# TCRT1010_VIS_pac.net
KiCad netlist of a schematic drawn in EAGLE
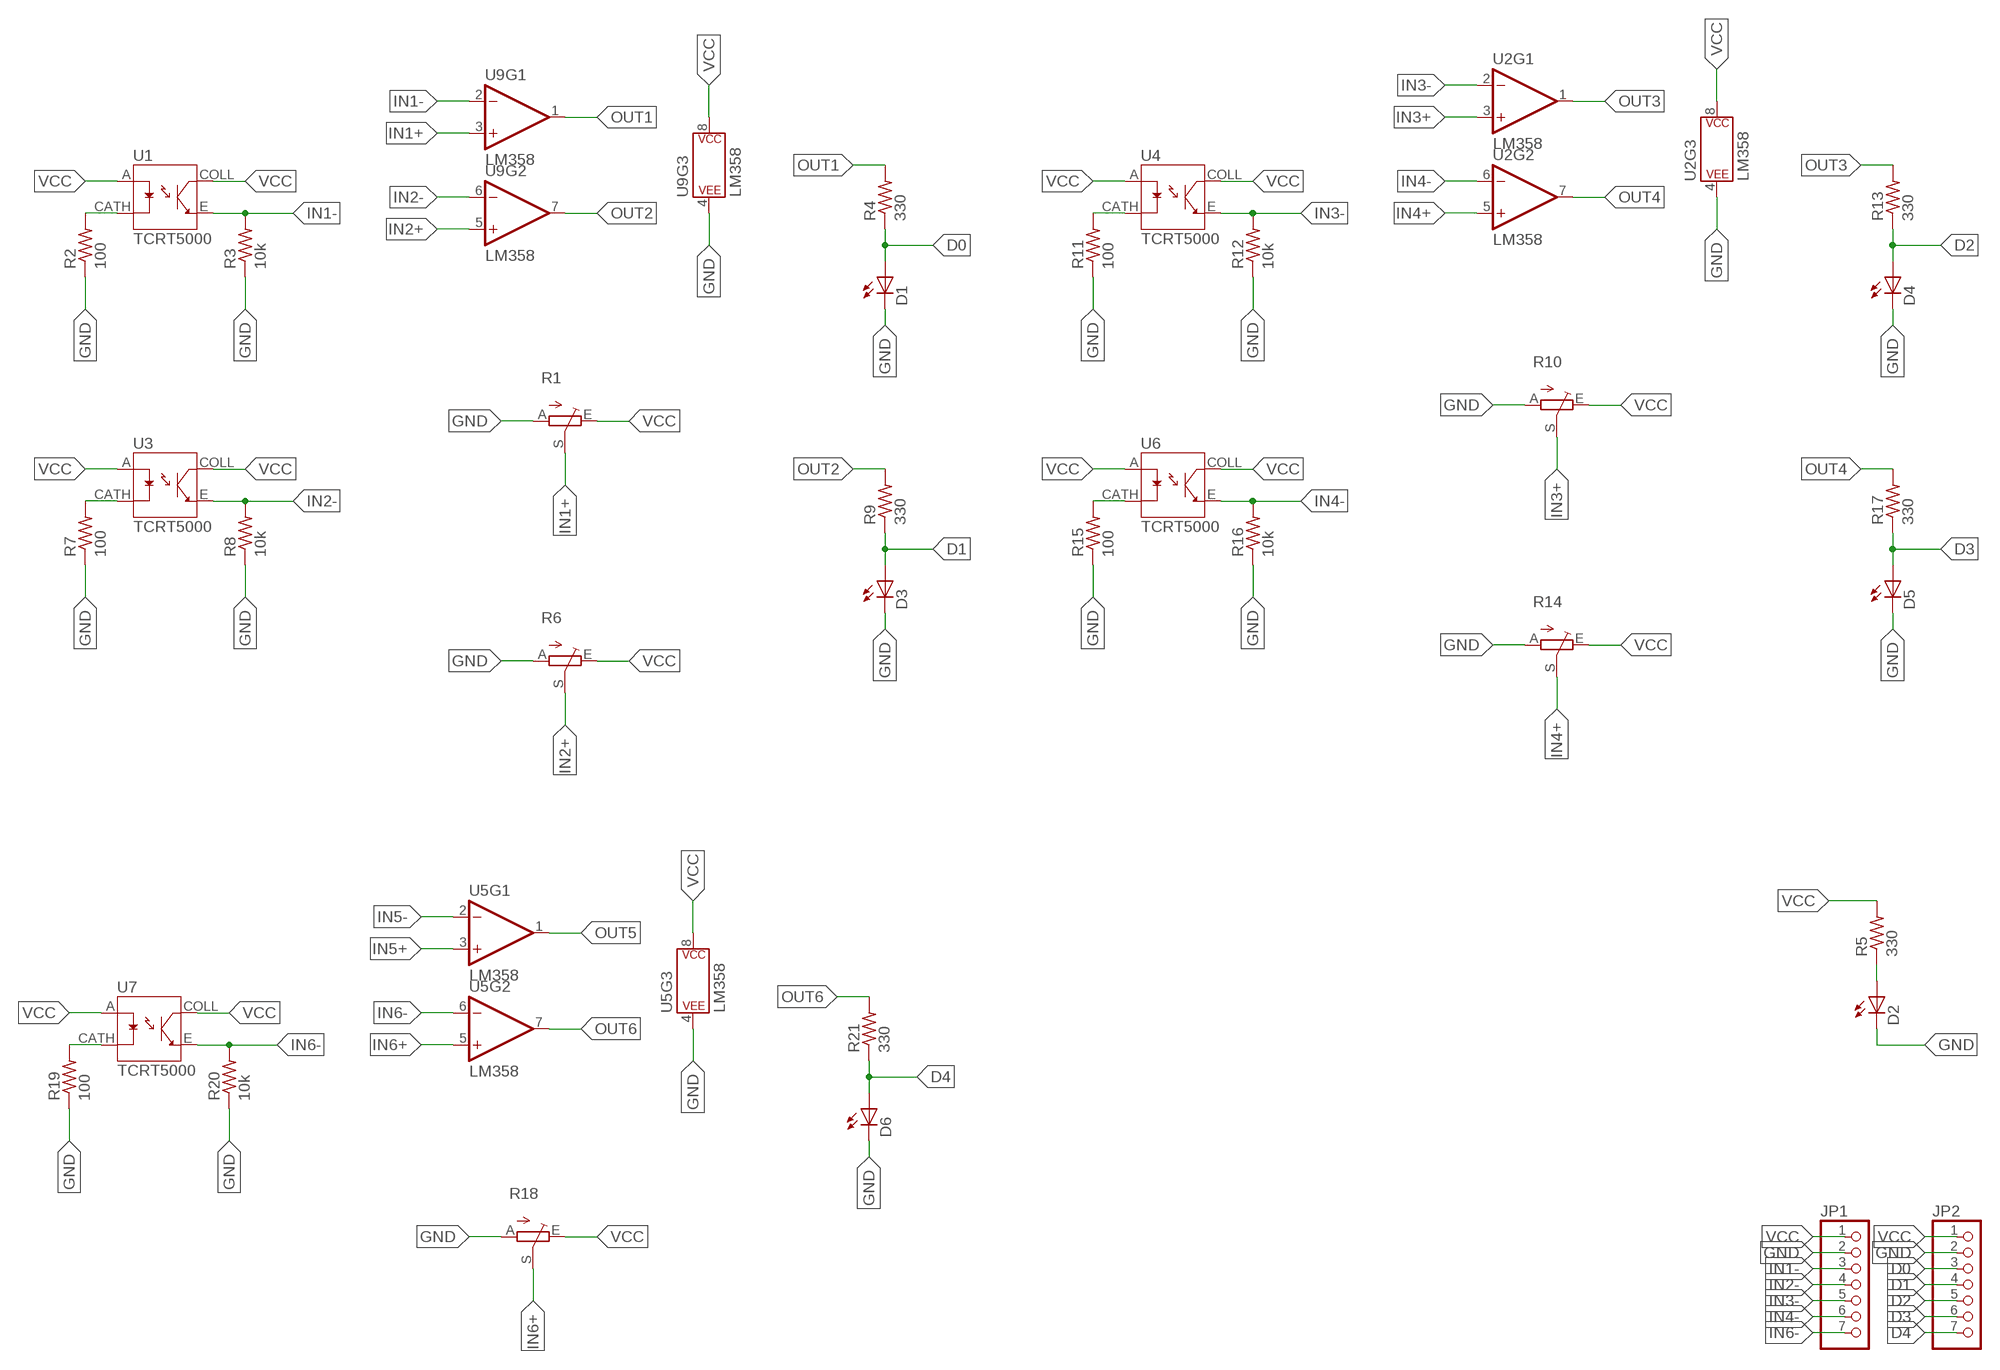
[diagram p0: schematic, sheet 1]

(export (version "E")
  (design (tool "Eeschema 10.0.6"))
  (components
    (comp (ref "D1")
      (value "LED5MM")
      (footprint "eagle-import:LED5MM")
      (libsource (lib "eagle-import") (part "LED5MM"))
    )
    (comp (ref "D2")
      (value "LED5MM")
      (footprint "eagle-import:LED5MM")
      (libsource (lib "eagle-import") (part "LED5MM"))
    )
    (comp (ref "D3")
      (value "LED5MM")
      (footprint "eagle-import:LED5MM")
      (libsource (lib "eagle-import") (part "LED5MM"))
    )
    (comp (ref "D4")
      (value "LED5MM")
      (footprint "eagle-import:LED5MM")
      (libsource (lib "eagle-import") (part "LED5MM"))
    )
    (comp (ref "D5")
      (value "LED5MM")
      (footprint "eagle-import:LED5MM")
      (libsource (lib "eagle-import") (part "LED5MM"))
    )
    (comp (ref "D6")
      (value "LED5MM")
      (footprint "eagle-import:LED5MM")
      (libsource (lib "eagle-import") (part "LED5MM"))
    )
    (comp (ref "JP1")
      (value "PINHD-1X7")
      (footprint "eagle-import:1X07")
      (libsource (lib "eagle-import") (part "PINHD-1X7"))
    )
    (comp (ref "JP2")
      (value "PINHD-1X7")
      (footprint "eagle-import:1X07")
      (libsource (lib "eagle-import") (part "PINHD-1X7"))
    )
    (comp (ref "R1")
      (value "TRIM_EU-CA6V")
      (footprint "eagle-import:CA6V")
      (libsource (lib "eagle-import") (part "TRIM_EU-CA6V"))
    )
    (comp (ref "R2")
      (value "100")
      (footprint "eagle-import:0204_7")
      (libsource (lib "eagle-import") (part "RES-7"))
    )
    (comp (ref "R3")
      (value "10k")
      (footprint "eagle-import:0204_7")
      (libsource (lib "eagle-import") (part "RES-7"))
    )
    (comp (ref "R4")
      (value "330")
      (footprint "eagle-import:0204_7")
      (libsource (lib "eagle-import") (part "RES-7"))
    )
    (comp (ref "R5")
      (value "330")
      (footprint "eagle-import:0204_7")
      (libsource (lib "eagle-import") (part "RES-7"))
    )
    (comp (ref "R6")
      (value "TRIM_EU-CA6V")
      (footprint "eagle-import:CA6V")
      (libsource (lib "eagle-import") (part "TRIM_EU-CA6V"))
    )
    (comp (ref "R7")
      (value "100")
      (footprint "eagle-import:0204_7")
      (libsource (lib "eagle-import") (part "RES-7"))
    )
    (comp (ref "R8")
      (value "10k")
      (footprint "eagle-import:0204_7")
      (libsource (lib "eagle-import") (part "RES-7"))
    )
    (comp (ref "R9")
      (value "330")
      (footprint "eagle-import:0204_7")
      (libsource (lib "eagle-import") (part "RES-7"))
    )
    (comp (ref "R10")
      (value "TRIM_EU-CA6V")
      (footprint "eagle-import:CA6V")
      (libsource (lib "eagle-import") (part "TRIM_EU-CA6V"))
    )
    (comp (ref "R11")
      (value "100")
      (footprint "eagle-import:0204_7")
      (libsource (lib "eagle-import") (part "RES-7"))
    )
    (comp (ref "R12")
      (value "10k")
      (footprint "eagle-import:0204_7")
      (libsource (lib "eagle-import") (part "RES-7"))
    )
    (comp (ref "R13")
      (value "330")
      (footprint "eagle-import:0204_7")
      (libsource (lib "eagle-import") (part "RES-7"))
    )
    (comp (ref "R14")
      (value "TRIM_EU-CA6V")
      (footprint "eagle-import:CA6V")
      (libsource (lib "eagle-import") (part "TRIM_EU-CA6V"))
    )
    (comp (ref "R15")
      (value "100")
      (footprint "eagle-import:0204_7")
      (libsource (lib "eagle-import") (part "RES-7"))
    )
    (comp (ref "R16")
      (value "10k")
      (footprint "eagle-import:0204_7")
      (libsource (lib "eagle-import") (part "RES-7"))
    )
    (comp (ref "R17")
      (value "330")
      (footprint "eagle-import:0204_7")
      (libsource (lib "eagle-import") (part "RES-7"))
    )
    (comp (ref "R18")
      (value "TRIM_EU-CA6V")
      (footprint "eagle-import:CA6V")
      (libsource (lib "eagle-import") (part "TRIM_EU-CA6V"))
    )
    (comp (ref "R19")
      (value "100")
      (footprint "eagle-import:0204_7")
      (libsource (lib "eagle-import") (part "RES-7"))
    )
    (comp (ref "R20")
      (value "10k")
      (footprint "eagle-import:0204_7")
      (libsource (lib "eagle-import") (part "RES-7"))
    )
    (comp (ref "R21")
      (value "330")
      (footprint "eagle-import:0204_7")
      (libsource (lib "eagle-import") (part "RES-7"))
    )
    (comp (ref "U1")
      (value "TCRT5000")
      (footprint "eagle-import:OPTO_TCRT5000")
      (fields (field (name "MF") "Vishay"))
      (libsource (lib "eagle-import") (part "TCRT5000"))
    )
    (comp (ref "U2")
      (value "LM358")
      (footprint "eagle-import:DIP08")
      (libsource (lib "eagle-import") (part "LM358"))
    )
    (comp (ref "U3")
      (value "TCRT5000")
      (footprint "eagle-import:OPTO_TCRT5000")
      (fields (field (name "MF") "Vishay"))
      (libsource (lib "eagle-import") (part "TCRT5000"))
    )
    (comp (ref "U4")
      (value "TCRT5000")
      (footprint "eagle-import:OPTO_TCRT5000")
      (fields (field (name "MF") "Vishay"))
      (libsource (lib "eagle-import") (part "TCRT5000"))
    )
    (comp (ref "U5")
      (value "LM358")
      (footprint "eagle-import:DIP08")
      (libsource (lib "eagle-import") (part "LM358"))
    )
    (comp (ref "U6")
      (value "TCRT5000")
      (footprint "eagle-import:OPTO_TCRT5000")
      (fields (field (name "MF") "Vishay"))
      (libsource (lib "eagle-import") (part "TCRT5000"))
    )
    (comp (ref "U7")
      (value "TCRT5000")
      (footprint "eagle-import:OPTO_TCRT5000")
      (fields (field (name "MF") "Vishay"))
      (libsource (lib "eagle-import") (part "TCRT5000"))
    )
    (comp (ref "U9")
      (value "LM358")
      (footprint "eagle-import:DIP08")
      (libsource (lib "eagle-import") (part "LM358"))
    )
  )
  (nets
    (net (code "1") (name "D0") (class "Default")
      (node (ref "D1") (pin "A") (pinfunction "A_A") (pintype "passive"))
      (node (ref "JP2") (pin "3") (pinfunction "3_3") (pintype "passive"))
      (node (ref "R4") (pin "1") (pinfunction "1_1") (pintype "passive"))
    )
    (net (code "2") (name "D1") (class "Default")
      (node (ref "D3") (pin "A") (pinfunction "A_A") (pintype "passive"))
      (node (ref "JP2") (pin "4") (pinfunction "4_4") (pintype "passive"))
      (node (ref "R9") (pin "1") (pinfunction "1_1") (pintype "passive"))
    )
    (net (code "3") (name "D2") (class "Default")
      (node (ref "D4") (pin "A") (pinfunction "A_A") (pintype "passive"))
      (node (ref "JP2") (pin "5") (pinfunction "5_5") (pintype "passive"))
      (node (ref "R13") (pin "1") (pinfunction "1_1") (pintype "passive"))
    )
    (net (code "4") (name "D3") (class "Default")
      (node (ref "D5") (pin "A") (pinfunction "A_A") (pintype "passive"))
      (node (ref "JP2") (pin "6") (pinfunction "6_6") (pintype "passive"))
      (node (ref "R17") (pin "1") (pinfunction "1_1") (pintype "passive"))
    )
    (net (code "5") (name "D4") (class "Default")
      (node (ref "D6") (pin "A") (pinfunction "A_A") (pintype "passive"))
      (node (ref "JP2") (pin "7") (pinfunction "7_7") (pintype "passive"))
      (node (ref "R21") (pin "1") (pinfunction "1_1") (pintype "passive"))
    )
    (net (code "6") (name "GND") (class "Default")
      (node (ref "D1") (pin "K") (pinfunction "C_K") (pintype "passive"))
      (node (ref "D2") (pin "K") (pinfunction "C_K") (pintype "passive"))
      (node (ref "D3") (pin "K") (pinfunction "C_K") (pintype "passive"))
      (node (ref "D4") (pin "K") (pinfunction "C_K") (pintype "passive"))
      (node (ref "D5") (pin "K") (pinfunction "C_K") (pintype "passive"))
      (node (ref "D6") (pin "K") (pinfunction "C_K") (pintype "passive"))
      (node (ref "JP1") (pin "2") (pinfunction "2_2") (pintype "passive"))
      (node (ref "JP2") (pin "2") (pinfunction "2_2") (pintype "passive"))
      (node (ref "R1") (pin "A") (pinfunction "A_A") (pintype "passive"))
      (node (ref "R10") (pin "A") (pinfunction "A_A") (pintype "passive"))
      (node (ref "R11") (pin "1") (pinfunction "1_1") (pintype "passive"))
      (node (ref "R12") (pin "1") (pinfunction "1_1") (pintype "passive"))
      (node (ref "R14") (pin "A") (pinfunction "A_A") (pintype "passive"))
      (node (ref "R15") (pin "1") (pinfunction "1_1") (pintype "passive"))
      (node (ref "R16") (pin "1") (pinfunction "1_1") (pintype "passive"))
      (node (ref "R18") (pin "A") (pinfunction "A_A") (pintype "passive"))
      (node (ref "R19") (pin "1") (pinfunction "1_1") (pintype "passive"))
      (node (ref "R2") (pin "1") (pinfunction "1_1") (pintype "passive"))
      (node (ref "R20") (pin "1") (pinfunction "1_1") (pintype "passive"))
      (node (ref "R3") (pin "1") (pinfunction "1_1") (pintype "passive"))
      (node (ref "R6") (pin "A") (pinfunction "A_A") (pintype "passive"))
      (node (ref "R7") (pin "1") (pinfunction "1_1") (pintype "passive"))
      (node (ref "R8") (pin "1") (pinfunction "1_1") (pintype "passive"))
      (node (ref "U2") (pin "4") (pinfunction "P$V-_4") (pintype "bidirectional"))
      (node (ref "U5") (pin "4") (pinfunction "P$V-_4") (pintype "bidirectional"))
      (node (ref "U9") (pin "4") (pinfunction "P$V-_4") (pintype "bidirectional"))
    )
    (net (code "7") (name "IN1+") (class "Default")
      (node (ref "R1") (pin "S") (pinfunction "S_S") (pintype "passive"))
      (node (ref "U9") (pin "3") (pinfunction "+IN_3") (pintype "input"))
    )
    (net (code "8") (name "IN1-") (class "Default")
      (node (ref "JP1") (pin "3") (pinfunction "3_3") (pintype "passive"))
      (node (ref "R3") (pin "2") (pinfunction "2_2") (pintype "passive"))
      (node (ref "U1") (pin "E") (pinfunction "E_E") (pintype "passive"))
      (node (ref "U9") (pin "2") (pinfunction "-IN_2") (pintype "input"))
    )
    (net (code "9") (name "IN2+") (class "Default")
      (node (ref "R6") (pin "S") (pinfunction "S_S") (pintype "passive"))
      (node (ref "U9") (pin "5") (pinfunction "+IN_5") (pintype "input"))
    )
    (net (code "10") (name "IN2-") (class "Default")
      (node (ref "JP1") (pin "4") (pinfunction "4_4") (pintype "passive"))
      (node (ref "R8") (pin "2") (pinfunction "2_2") (pintype "passive"))
      (node (ref "U3") (pin "E") (pinfunction "E_E") (pintype "passive"))
      (node (ref "U9") (pin "6") (pinfunction "-IN_6") (pintype "input"))
    )
    (net (code "11") (name "IN3+") (class "Default")
      (node (ref "R10") (pin "S") (pinfunction "S_S") (pintype "passive"))
      (node (ref "U2") (pin "3") (pinfunction "+IN_3") (pintype "input"))
    )
    (net (code "12") (name "IN3-") (class "Default")
      (node (ref "JP1") (pin "5") (pinfunction "5_5") (pintype "passive"))
      (node (ref "R12") (pin "2") (pinfunction "2_2") (pintype "passive"))
      (node (ref "U2") (pin "2") (pinfunction "-IN_2") (pintype "input"))
      (node (ref "U4") (pin "E") (pinfunction "E_E") (pintype "passive"))
    )
    (net (code "13") (name "IN4+") (class "Default")
      (node (ref "R14") (pin "S") (pinfunction "S_S") (pintype "passive"))
      (node (ref "U2") (pin "5") (pinfunction "+IN_5") (pintype "input"))
    )
    (net (code "14") (name "IN4-") (class "Default")
      (node (ref "JP1") (pin "6") (pinfunction "6_6") (pintype "passive"))
      (node (ref "R16") (pin "2") (pinfunction "2_2") (pintype "passive"))
      (node (ref "U2") (pin "6") (pinfunction "-IN_6") (pintype "input"))
      (node (ref "U6") (pin "E") (pinfunction "E_E") (pintype "passive"))
    )
    (net (code "15") (name "IN5+") (class "Default")
      (node (ref "U5") (pin "3") (pinfunction "+IN_3") (pintype "input"))
    )
    (net (code "16") (name "IN5-") (class "Default")
      (node (ref "U5") (pin "2") (pinfunction "-IN_2") (pintype "input"))
    )
    (net (code "17") (name "IN6+") (class "Default")
      (node (ref "R18") (pin "S") (pinfunction "S_S") (pintype "passive"))
      (node (ref "U5") (pin "5") (pinfunction "+IN_5") (pintype "input"))
    )
    (net (code "18") (name "IN6-") (class "Default")
      (node (ref "JP1") (pin "7") (pinfunction "7_7") (pintype "passive"))
      (node (ref "R20") (pin "2") (pinfunction "2_2") (pintype "passive"))
      (node (ref "U5") (pin "6") (pinfunction "-IN_6") (pintype "input"))
      (node (ref "U7") (pin "E") (pinfunction "E_E") (pintype "passive"))
    )
    (net (code "19") (name "Net-(D2-PadA)") (class "Default")
      (node (ref "D2") (pin "A") (pinfunction "A_A") (pintype "passive"))
      (node (ref "R5") (pin "1") (pinfunction "1_1") (pintype "passive"))
    )
    (net (code "20") (name "Net-(R2-Pad2)") (class "Default")
      (node (ref "R2") (pin "2") (pinfunction "2_2") (pintype "passive"))
      (node (ref "U1") (pin "CATH") (pinfunction "CATH_CATH") (pintype "passive"))
    )
    (net (code "21") (name "Net-(R7-Pad2)") (class "Default")
      (node (ref "R7") (pin "2") (pinfunction "2_2") (pintype "passive"))
      (node (ref "U3") (pin "CATH") (pinfunction "CATH_CATH") (pintype "passive"))
    )
    (net (code "22") (name "Net-(R11-Pad2)") (class "Default")
      (node (ref "R11") (pin "2") (pinfunction "2_2") (pintype "passive"))
      (node (ref "U4") (pin "CATH") (pinfunction "CATH_CATH") (pintype "passive"))
    )
    (net (code "23") (name "Net-(R15-Pad2)") (class "Default")
      (node (ref "R15") (pin "2") (pinfunction "2_2") (pintype "passive"))
      (node (ref "U6") (pin "CATH") (pinfunction "CATH_CATH") (pintype "passive"))
    )
    (net (code "24") (name "Net-(R19-Pad2)") (class "Default")
      (node (ref "R19") (pin "2") (pinfunction "2_2") (pintype "passive"))
      (node (ref "U7") (pin "CATH") (pinfunction "CATH_CATH") (pintype "passive"))
    )
    (net (code "25") (name "OUT1") (class "Default")
      (node (ref "R4") (pin "2") (pinfunction "2_2") (pintype "passive"))
      (node (ref "U9") (pin "1") (pinfunction "OUT_1") (pintype "output"))
    )
    (net (code "26") (name "OUT2") (class "Default")
      (node (ref "R9") (pin "2") (pinfunction "2_2") (pintype "passive"))
      (node (ref "U9") (pin "7") (pinfunction "OUT_7") (pintype "output"))
    )
    (net (code "27") (name "OUT3") (class "Default")
      (node (ref "R13") (pin "2") (pinfunction "2_2") (pintype "passive"))
      (node (ref "U2") (pin "1") (pinfunction "OUT_1") (pintype "output"))
    )
    (net (code "28") (name "OUT4") (class "Default")
      (node (ref "R17") (pin "2") (pinfunction "2_2") (pintype "passive"))
      (node (ref "U2") (pin "7") (pinfunction "OUT_7") (pintype "output"))
    )
    (net (code "29") (name "OUT5") (class "Default")
      (node (ref "U5") (pin "1") (pinfunction "OUT_1") (pintype "output"))
    )
    (net (code "30") (name "OUT6") (class "Default")
      (node (ref "R21") (pin "2") (pinfunction "2_2") (pintype "passive"))
      (node (ref "U5") (pin "7") (pinfunction "OUT_7") (pintype "output"))
    )
    (net (code "31") (name "VCC") (class "Default")
      (node (ref "JP1") (pin "1") (pinfunction "1_1") (pintype "passive"))
      (node (ref "JP2") (pin "1") (pinfunction "1_1") (pintype "passive"))
      (node (ref "R1") (pin "E") (pinfunction "E_E") (pintype "passive"))
      (node (ref "R10") (pin "E") (pinfunction "E_E") (pintype "passive"))
      (node (ref "R14") (pin "E") (pinfunction "E_E") (pintype "passive"))
      (node (ref "R18") (pin "E") (pinfunction "E_E") (pintype "passive"))
      (node (ref "R5") (pin "2") (pinfunction "2_2") (pintype "passive"))
      (node (ref "R6") (pin "E") (pinfunction "E_E") (pintype "passive"))
      (node (ref "U1") (pin "A") (pinfunction "A_A") (pintype "passive"))
      (node (ref "U1") (pin "COLL") (pinfunction "COLL_COLL") (pintype "passive"))
      (node (ref "U2") (pin "8") (pinfunction "P$V+_8") (pintype "bidirectional"))
      (node (ref "U3") (pin "A") (pinfunction "A_A") (pintype "passive"))
      (node (ref "U3") (pin "COLL") (pinfunction "COLL_COLL") (pintype "passive"))
      (node (ref "U4") (pin "A") (pinfunction "A_A") (pintype "passive"))
      (node (ref "U4") (pin "COLL") (pinfunction "COLL_COLL") (pintype "passive"))
      (node (ref "U5") (pin "8") (pinfunction "P$V+_8") (pintype "bidirectional"))
      (node (ref "U6") (pin "A") (pinfunction "A_A") (pintype "passive"))
      (node (ref "U6") (pin "COLL") (pinfunction "COLL_COLL") (pintype "passive"))
      (node (ref "U7") (pin "A") (pinfunction "A_A") (pintype "passive"))
      (node (ref "U7") (pin "COLL") (pinfunction "COLL_COLL") (pintype "passive"))
      (node (ref "U9") (pin "8") (pinfunction "P$V+_8") (pintype "bidirectional"))
    )
  )
)
